# sevenSeg4_atmega_5C_noGND.net
KiCad netlist of a schematic drawn in EAGLE
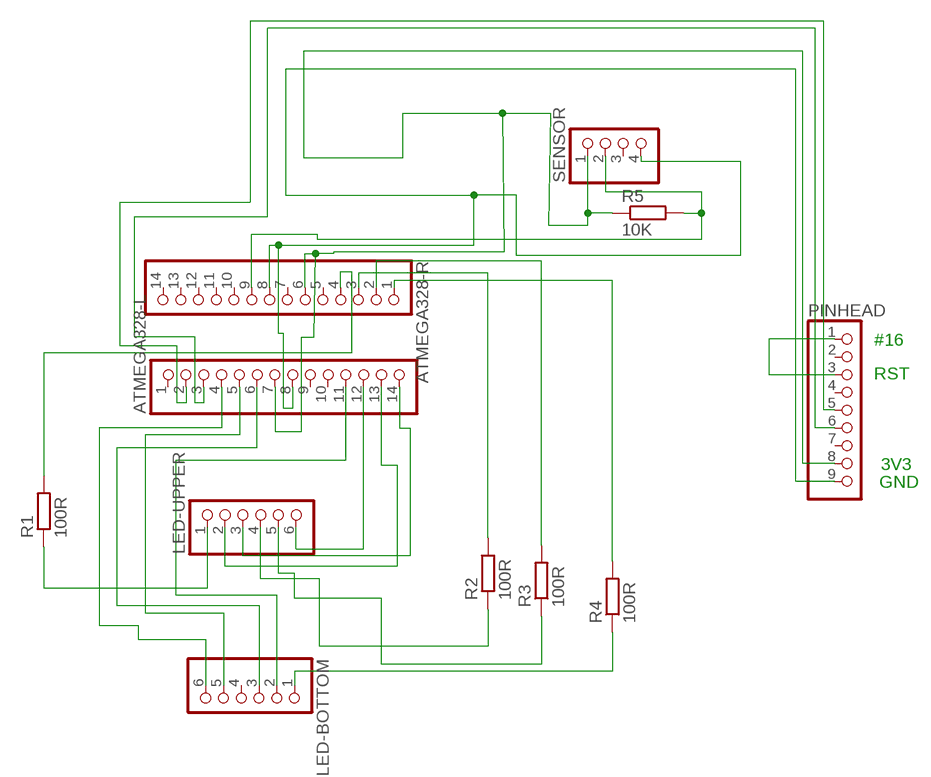
[diagram p0: schematic, sheet 1]

(export (version "E")
  (design (tool "Eeschema 10.0.6"))
  (components
    (comp (ref "ATMEGA328-L")
      (value "PINHD-1X14")
      (footprint "eagle-import:1X14")
      (libsource (lib "eagle-import") (part "PINHD-1X14"))
    )
    (comp (ref "ATMEGA328-R")
      (value "PINHD-1X14")
      (footprint "eagle-import:1X14")
      (libsource (lib "eagle-import") (part "PINHD-1X14"))
    )
    (comp (ref "LED-BOTTOM")
      (value "PINHD-1X6")
      (footprint "eagle-import:1X06")
      (libsource (lib "eagle-import") (part "PINHD-1X6"))
    )
    (comp (ref "LED-UPPER")
      (value "PINHD-1X6")
      (footprint "eagle-import:1X06")
      (libsource (lib "eagle-import") (part "PINHD-1X6"))
    )
    (comp (ref "PINHEAD")
      (value "PINHD-1X9")
      (footprint "eagle-import:1X09")
      (libsource (lib "eagle-import") (part "PINHD-1X9"))
    )
    (comp (ref "R1")
      (value "100R")
      (footprint "eagle-import:R0603")
      (libsource (lib "eagle-import") (part "R-EU_R0603"))
    )
    (comp (ref "R2")
      (value "100R")
      (footprint "eagle-import:R0603")
      (libsource (lib "eagle-import") (part "R-EU_R0603"))
    )
    (comp (ref "R3")
      (value "100R")
      (footprint "eagle-import:R0603")
      (libsource (lib "eagle-import") (part "R-EU_R0603"))
    )
    (comp (ref "R4")
      (value "100R")
      (footprint "eagle-import:R0603")
      (libsource (lib "eagle-import") (part "R-EU_R0603"))
    )
    (comp (ref "R5")
      (value "10K")
      (footprint "eagle-import:R0603")
      (libsource (lib "eagle-import") (part "R-EU_R0603"))
    )
    (comp (ref "SENSOR")
      (value "PINHD-1X4")
      (footprint "eagle-import:1X04")
      (libsource (lib "eagle-import") (part "PINHD-1X4"))
    )
  )
  (nets
    (net (code "1") (name "Net-(ATMEGA328-L-Pad2)") (class "Default")
      (node (ref "ATMEGA328-L") (pin "2") (pinfunction "2_2") (pintype "passive"))
      (node (ref "PINHEAD") (pin "5") (pinfunction "5_5") (pintype "passive"))
    )
    (net (code "2") (name "Net-(ATMEGA328-L-Pad3)") (class "Default")
      (node (ref "ATMEGA328-L") (pin "3") (pinfunction "3_3") (pintype "passive"))
      (node (ref "PINHEAD") (pin "6") (pinfunction "6_6") (pintype "passive"))
    )
    (net (code "3") (name "Net-(ATMEGA328-L-Pad4)") (class "Default")
      (node (ref "ATMEGA328-L") (pin "4") (pinfunction "4_4") (pintype "passive"))
      (node (ref "LED-BOTTOM") (pin "6") (pinfunction "6_6") (pintype "passive"))
    )
    (net (code "4") (name "Net-(ATMEGA328-L-Pad5)") (class "Default")
      (node (ref "ATMEGA328-L") (pin "5") (pinfunction "5_5") (pintype "passive"))
      (node (ref "LED-BOTTOM") (pin "5") (pinfunction "5_5") (pintype "passive"))
    )
    (net (code "5") (name "Net-(ATMEGA328-L-Pad6)") (class "Default")
      (node (ref "ATMEGA328-L") (pin "6") (pinfunction "6_6") (pintype "passive"))
      (node (ref "LED-BOTTOM") (pin "3") (pinfunction "3_3") (pintype "passive"))
    )
    (net (code "6") (name "Net-(ATMEGA328-L-Pad7)") (class "Default")
      (node (ref "ATMEGA328-L") (pin "7") (pinfunction "7_7") (pintype "passive"))
      (node (ref "ATMEGA328-R") (pin "6") (pinfunction "6_6") (pintype "passive"))
      (node (ref "PINHEAD") (pin "8") (pinfunction "8_8") (pintype "passive"))
      (node (ref "R5") (pin "1") (pinfunction "1_1") (pintype "passive"))
      (node (ref "SENSOR") (pin "1") (pinfunction "1_1") (pintype "passive"))
    )
    (net (code "7") (name "Net-(ATMEGA328-L-Pad8)") (class "Default")
      (node (ref "ATMEGA328-L") (pin "8") (pinfunction "8_8") (pintype "passive"))
      (node (ref "ATMEGA328-R") (pin "8") (pinfunction "8_8") (pintype "passive"))
      (node (ref "PINHEAD") (pin "9") (pinfunction "9_9") (pintype "passive"))
      (node (ref "SENSOR") (pin "4") (pinfunction "4_4") (pintype "passive"))
    )
    (net (code "8") (name "Net-(ATMEGA328-L-Pad11)") (class "Default")
      (node (ref "ATMEGA328-L") (pin "11") (pinfunction "11_11") (pintype "passive"))
      (node (ref "LED-BOTTOM") (pin "2") (pinfunction "2_2") (pintype "passive"))
    )
    (net (code "9") (name "Net-(ATMEGA328-L-Pad12)") (class "Default")
      (node (ref "ATMEGA328-L") (pin "12") (pinfunction "12_12") (pintype "passive"))
      (node (ref "LED-UPPER") (pin "6") (pinfunction "6_6") (pintype "passive"))
    )
    (net (code "10") (name "Net-(ATMEGA328-L-Pad13)") (class "Default")
      (node (ref "ATMEGA328-L") (pin "13") (pinfunction "13_13") (pintype "passive"))
      (node (ref "LED-UPPER") (pin "2") (pinfunction "2_2") (pintype "passive"))
    )
    (net (code "11") (name "Net-(ATMEGA328-L-Pad14)") (class "Default")
      (node (ref "ATMEGA328-L") (pin "14") (pinfunction "14_14") (pintype "passive"))
      (node (ref "LED-UPPER") (pin "3") (pinfunction "3_3") (pintype "passive"))
    )
    (net (code "12") (name "Net-(ATMEGA328-R-Pad1)") (class "Default")
      (node (ref "ATMEGA328-R") (pin "1") (pinfunction "1_1") (pintype "passive"))
      (node (ref "R4") (pin "2") (pinfunction "2_2") (pintype "passive"))
    )
    (net (code "13") (name "Net-(ATMEGA328-R-Pad2)") (class "Default")
      (node (ref "ATMEGA328-R") (pin "2") (pinfunction "2_2") (pintype "passive"))
      (node (ref "R3") (pin "2") (pinfunction "2_2") (pintype "passive"))
    )
    (net (code "14") (name "Net-(ATMEGA328-R-Pad3)") (class "Default")
      (node (ref "ATMEGA328-R") (pin "3") (pinfunction "3_3") (pintype "passive"))
      (node (ref "R2") (pin "2") (pinfunction "2_2") (pintype "passive"))
    )
    (net (code "15") (name "Net-(ATMEGA328-R-Pad4)") (class "Default")
      (node (ref "ATMEGA328-R") (pin "4") (pinfunction "4_4") (pintype "passive"))
      (node (ref "R1") (pin "2") (pinfunction "2_2") (pintype "passive"))
    )
    (net (code "16") (name "Net-(ATMEGA328-R-Pad9)") (class "Default")
      (node (ref "ATMEGA328-R") (pin "9") (pinfunction "9_9") (pintype "passive"))
      (node (ref "R5") (pin "2") (pinfunction "2_2") (pintype "passive"))
      (node (ref "SENSOR") (pin "2") (pinfunction "2_2") (pintype "passive"))
    )
    (net (code "17") (name "Net-(LED-BOTTOM-Pad1)") (class "Default")
      (node (ref "LED-BOTTOM") (pin "1") (pinfunction "1_1") (pintype "passive"))
      (node (ref "R4") (pin "1") (pinfunction "1_1") (pintype "passive"))
    )
    (net (code "18") (name "Net-(LED-UPPER-Pad1)") (class "Default")
      (node (ref "LED-UPPER") (pin "1") (pinfunction "1_1") (pintype "passive"))
      (node (ref "R1") (pin "1") (pinfunction "1_1") (pintype "passive"))
    )
    (net (code "19") (name "Net-(LED-UPPER-Pad4)") (class "Default")
      (node (ref "LED-UPPER") (pin "4") (pinfunction "4_4") (pintype "passive"))
      (node (ref "R2") (pin "1") (pinfunction "1_1") (pintype "passive"))
    )
    (net (code "20") (name "Net-(LED-UPPER-Pad5)") (class "Default")
      (node (ref "LED-UPPER") (pin "5") (pinfunction "5_5") (pintype "passive"))
      (node (ref "R3") (pin "1") (pinfunction "1_1") (pintype "passive"))
    )
    (net (code "21") (name "Net-(PINHEAD-Pad1)") (class "Default")
      (node (ref "PINHEAD") (pin "1") (pinfunction "1_1") (pintype "passive"))
      (node (ref "PINHEAD") (pin "3") (pinfunction "3_3") (pintype "passive"))
    )
    (net (code "22") (name "unconnected-(ATMEGA328-L-Pad1)") (class "Default")
      (node (ref "ATMEGA328-L") (pin "1") (pinfunction "1_1") (pintype "passive"))
    )
    (net (code "23") (name "unconnected-(ATMEGA328-L-Pad9)") (class "Default")
      (node (ref "ATMEGA328-L") (pin "9") (pinfunction "9_9") (pintype "passive"))
    )
    (net (code "24") (name "unconnected-(ATMEGA328-L-Pad10)") (class "Default")
      (node (ref "ATMEGA328-L") (pin "10") (pinfunction "10_10") (pintype "passive"))
    )
    (net (code "25") (name "unconnected-(ATMEGA328-R-Pad5)") (class "Default")
      (node (ref "ATMEGA328-R") (pin "5") (pinfunction "5_5") (pintype "passive"))
    )
    (net (code "26") (name "unconnected-(ATMEGA328-R-Pad7)") (class "Default")
      (node (ref "ATMEGA328-R") (pin "7") (pinfunction "7_7") (pintype "passive"))
    )
    (net (code "27") (name "unconnected-(ATMEGA328-R-Pad10)") (class "Default")
      (node (ref "ATMEGA328-R") (pin "10") (pinfunction "10_10") (pintype "passive"))
    )
    (net (code "28") (name "unconnected-(ATMEGA328-R-Pad11)") (class "Default")
      (node (ref "ATMEGA328-R") (pin "11") (pinfunction "11_11") (pintype "passive"))
    )
    (net (code "29") (name "unconnected-(ATMEGA328-R-Pad12)") (class "Default")
      (node (ref "ATMEGA328-R") (pin "12") (pinfunction "12_12") (pintype "passive"))
    )
    (net (code "30") (name "unconnected-(ATMEGA328-R-Pad13)") (class "Default")
      (node (ref "ATMEGA328-R") (pin "13") (pinfunction "13_13") (pintype "passive"))
    )
    (net (code "31") (name "unconnected-(ATMEGA328-R-Pad14)") (class "Default")
      (node (ref "ATMEGA328-R") (pin "14") (pinfunction "14_14") (pintype "passive"))
    )
    (net (code "32") (name "unconnected-(LED-BOTTOM-Pad4)") (class "Default")
      (node (ref "LED-BOTTOM") (pin "4") (pinfunction "4_4") (pintype "passive"))
    )
    (net (code "33") (name "unconnected-(PINHEAD-Pad2)") (class "Default")
      (node (ref "PINHEAD") (pin "2") (pinfunction "2_2") (pintype "passive"))
    )
    (net (code "34") (name "unconnected-(PINHEAD-Pad4)") (class "Default")
      (node (ref "PINHEAD") (pin "4") (pinfunction "4_4") (pintype "passive"))
    )
    (net (code "35") (name "unconnected-(PINHEAD-Pad7)") (class "Default")
      (node (ref "PINHEAD") (pin "7") (pinfunction "7_7") (pintype "passive"))
    )
    (net (code "36") (name "unconnected-(SENSOR-Pad3)") (class "Default")
      (node (ref "SENSOR") (pin "3") (pinfunction "3_3") (pintype "passive"))
    )
  )
)
